# 130820_I_T_V_AriloRX_FINAL.net
KiCad netlist of a schematic drawn in EAGLE
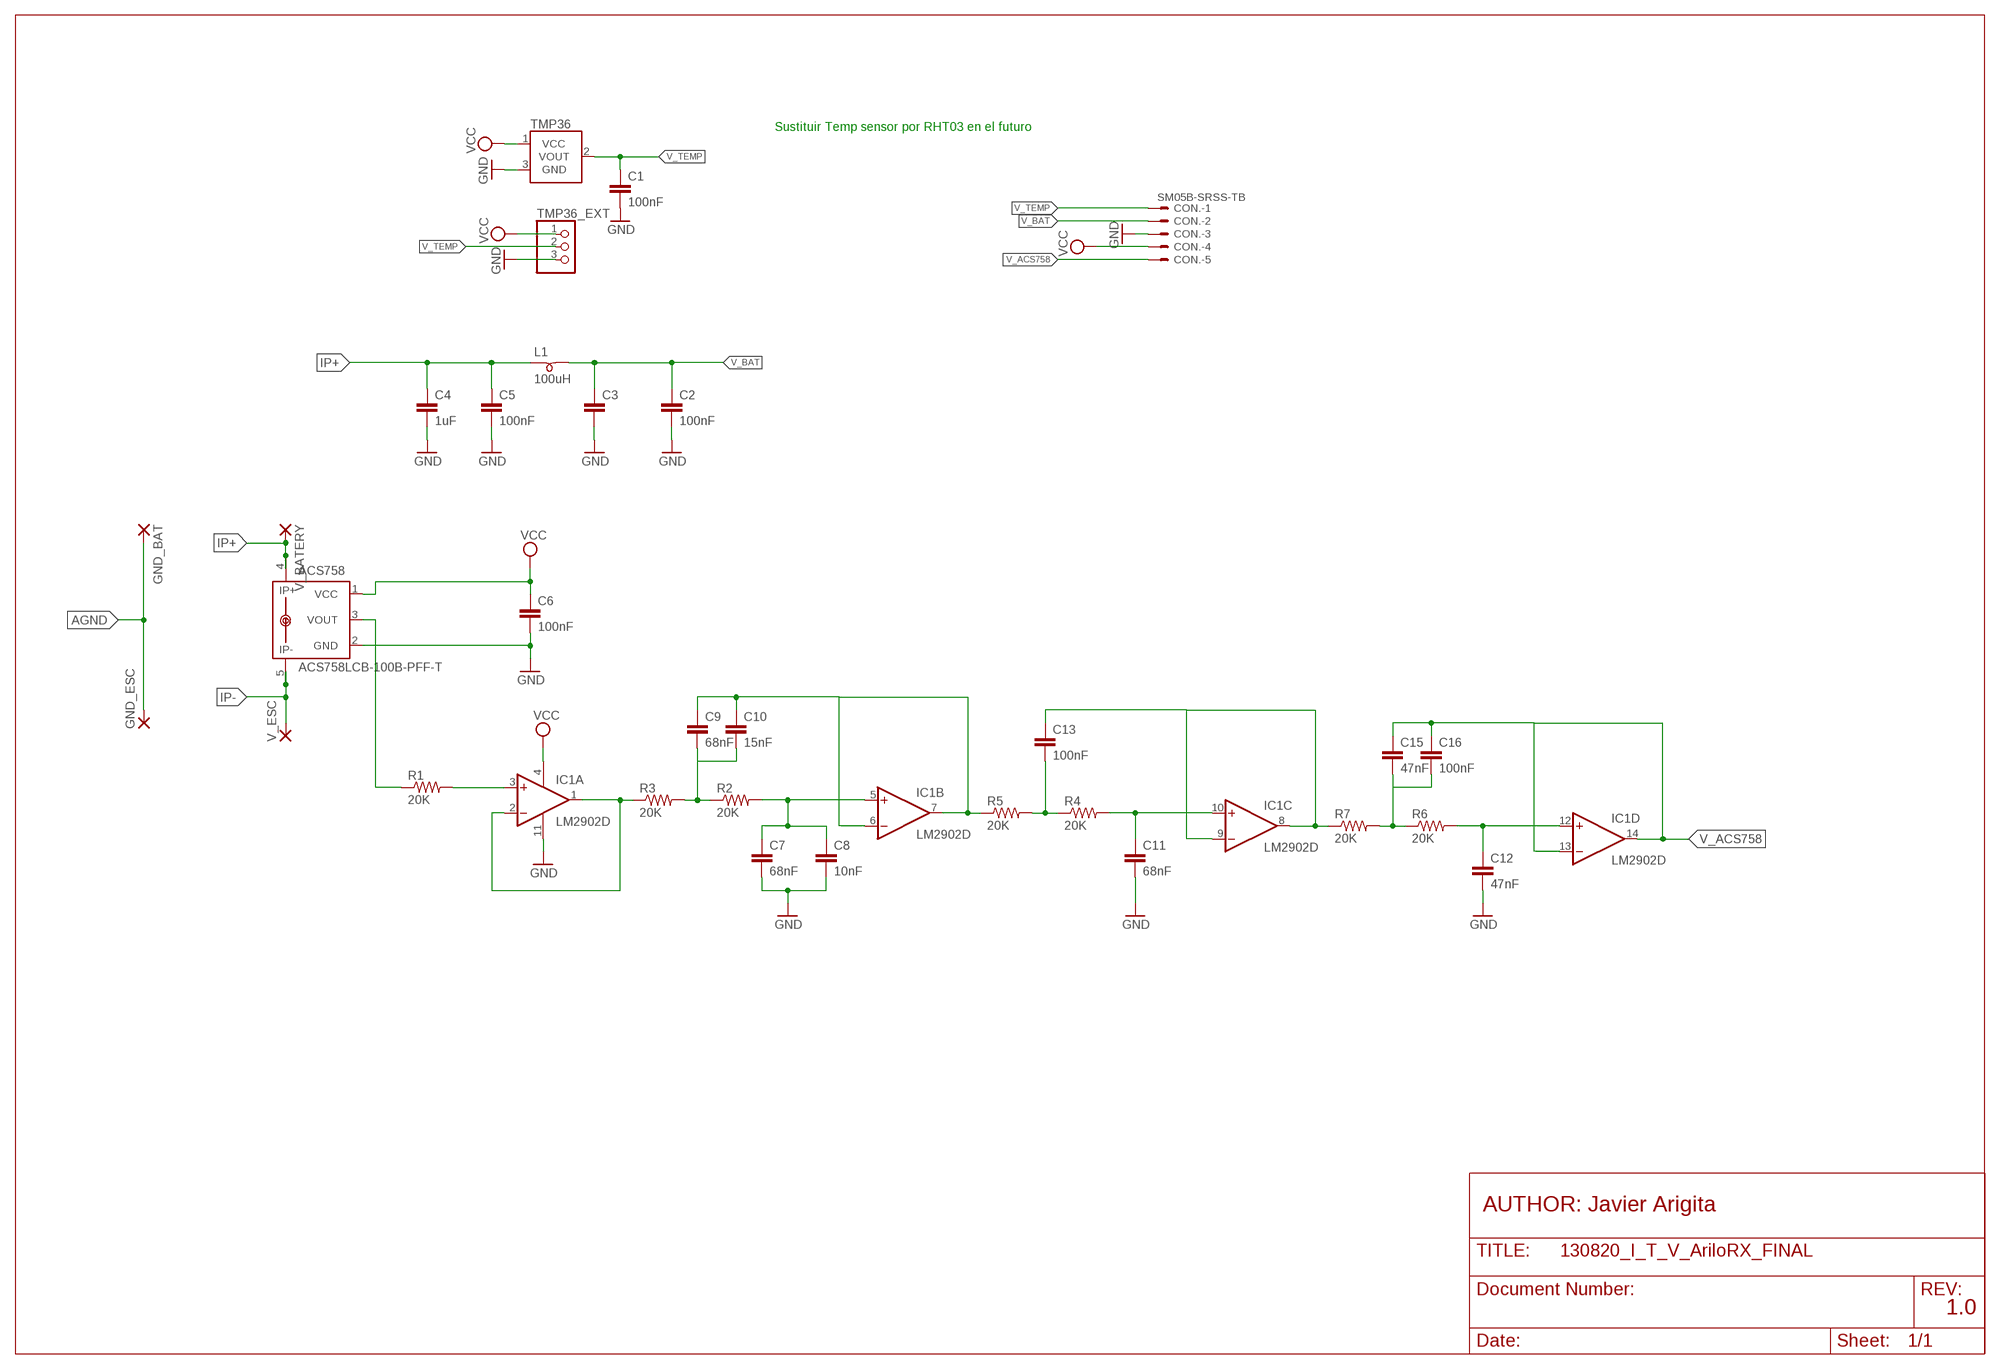
[diagram p0: schematic, sheet 1]

(export (version "E")
  (design (tool "Eeschema 10.0.6"))
  (components
    (comp (ref "ACS758")
      (value "ACS758LCB-100B-PFF-T")
      (footprint "eagle-import:CB-PFF")
      (libsource (lib "eagle-import") (part "ACS758LCB-100B-PFF-T"))
    )
    (comp (ref "C1")
      (value "100nF")
      (footprint "eagle-import:C0805")
      (libsource (lib "eagle-import") (part "C-EUC0805"))
    )
    (comp (ref "C2")
      (value "100nF")
      (footprint "eagle-import:C0805")
      (libsource (lib "eagle-import") (part "C-EUC0805"))
    )
    (comp (ref "C3")
      (value "C-EUC3216")
      (footprint "eagle-import:C3216")
      (libsource (lib "eagle-import") (part "C-EUC3216"))
    )
    (comp (ref "C4")
      (value "1uF")
      (footprint "eagle-import:C3216")
      (libsource (lib "eagle-import") (part "C-EUC3216"))
    )
    (comp (ref "C5")
      (value "100nF")
      (footprint "eagle-import:C0805")
      (libsource (lib "eagle-import") (part "C-EUC0805"))
    )
    (comp (ref "C6")
      (value "100nF")
      (footprint "eagle-import:C0805")
      (libsource (lib "eagle-import") (part "C-EUC0805"))
    )
    (comp (ref "C7")
      (value "68nF")
      (footprint "eagle-import:C0805")
      (libsource (lib "eagle-import") (part "C-EUC0805"))
    )
    (comp (ref "C8")
      (value "10nF")
      (footprint "eagle-import:C0805")
      (libsource (lib "eagle-import") (part "C-EUC0805"))
    )
    (comp (ref "C9")
      (value "68nF")
      (footprint "eagle-import:C0805")
      (libsource (lib "eagle-import") (part "C-EUC0805"))
    )
    (comp (ref "C10")
      (value "15nF")
      (footprint "eagle-import:C0805")
      (libsource (lib "eagle-import") (part "C-EUC0805"))
    )
    (comp (ref "C11")
      (value "68nF")
      (footprint "eagle-import:C0805")
      (libsource (lib "eagle-import") (part "C-EUC0805"))
    )
    (comp (ref "C12")
      (value "47nF")
      (footprint "eagle-import:C0805")
      (libsource (lib "eagle-import") (part "C-EUC0805"))
    )
    (comp (ref "C13")
      (value "100nF")
      (footprint "eagle-import:C0805")
      (libsource (lib "eagle-import") (part "C-EUC0805"))
    )
    (comp (ref "C15")
      (value "47nF")
      (footprint "eagle-import:C0805")
      (libsource (lib "eagle-import") (part "C-EUC0805"))
    )
    (comp (ref "C16")
      (value "100nF")
      (footprint "eagle-import:C0805")
      (libsource (lib "eagle-import") (part "C-EUC0805"))
    )
    (comp (ref "CON.")
      (value "SM05B-SRSS-TB")
      (footprint "eagle-import:SM05B-SRSS-TB")
      (libsource (lib "eagle-import") (part "?M05B-SRSS-TBS"))
    )
    (comp (ref "GND_BAT")
      (value "SMD5")
      (footprint "eagle-import:SMD2,54-5,08")
      (libsource (lib "eagle-import") (part "SMD5"))
    )
    (comp (ref "GND_ESC")
      (value "SMD5")
      (footprint "eagle-import:SMD2,54-5,08")
      (libsource (lib "eagle-import") (part "SMD5"))
    )
    (comp (ref "IC1")
      (value "LM2902D")
      (footprint "eagle-import:SO14")
      (libsource (lib "eagle-import") (part "LM2902D"))
    )
    (comp (ref "L1")
      (value "100uH")
      (footprint "eagle-import:SM-B5")
      (libsource (lib "eagle-import") (part "SM-B5"))
    )
    (comp (ref "R1")
      (value "20K")
      (footprint "eagle-import:R0805")
      (libsource (lib "eagle-import") (part "RESISTOR0805"))
    )
    (comp (ref "R2")
      (value "20K")
      (footprint "eagle-import:R0805")
      (libsource (lib "eagle-import") (part "RESISTOR0805"))
    )
    (comp (ref "R3")
      (value "20K")
      (footprint "eagle-import:R0805")
      (libsource (lib "eagle-import") (part "RESISTOR0805"))
    )
    (comp (ref "R4")
      (value "20K")
      (footprint "eagle-import:R0805")
      (libsource (lib "eagle-import") (part "RESISTOR0805"))
    )
    (comp (ref "R5")
      (value "20K")
      (footprint "eagle-import:R0805")
      (libsource (lib "eagle-import") (part "RESISTOR0805"))
    )
    (comp (ref "R6")
      (value "20K")
      (footprint "eagle-import:R0805")
      (libsource (lib "eagle-import") (part "RESISTOR0805"))
    )
    (comp (ref "R7")
      (value "20K")
      (footprint "eagle-import:R0805")
      (libsource (lib "eagle-import") (part "RESISTOR0805"))
    )
    (comp (ref "TMP36")
      (value "TMP36GT9")
      (footprint "eagle-import:TO-92")
      (libsource (lib "eagle-import") (part "TMP36GT9"))
    )
    (comp (ref "TMP36_EXT")
      (value "PINHD-1X3")
      (footprint "eagle-import:1X03")
      (libsource (lib "eagle-import") (part "PINHD-1X3"))
    )
    (comp (ref "V_BATERY")
      (value "SMD5")
      (footprint "eagle-import:SMD2,54-5,08")
      (libsource (lib "eagle-import") (part "SMD5"))
    )
    (comp (ref "V_ESC")
      (value "SMD5")
      (footprint "eagle-import:SMD2,54-5,08")
      (libsource (lib "eagle-import") (part "SMD5"))
    )
  )
  (nets
    (net (code "1") (name "AGND") (class "Default")
      (node (ref "GND_BAT") (pin "1") (pinfunction "P_1") (pintype "passive"))
      (node (ref "GND_ESC") (pin "1") (pinfunction "P_1") (pintype "passive"))
    )
    (net (code "2") (name "GND") (class "Default")
      (node (ref "ACS758") (pin "2") (pinfunction "GND_2") (pintype "power_in"))
      (node (ref "C1") (pin "2") (pinfunction "2_2") (pintype "passive"))
      (node (ref "C11") (pin "2") (pinfunction "2_2") (pintype "passive"))
      (node (ref "C12") (pin "2") (pinfunction "2_2") (pintype "passive"))
      (node (ref "C2") (pin "2") (pinfunction "2_2") (pintype "passive"))
      (node (ref "C3") (pin "2") (pinfunction "2_2") (pintype "passive"))
      (node (ref "C4") (pin "2") (pinfunction "2_2") (pintype "passive"))
      (node (ref "C5") (pin "2") (pinfunction "2_2") (pintype "passive"))
      (node (ref "C6") (pin "2") (pinfunction "2_2") (pintype "passive"))
      (node (ref "C7") (pin "2") (pinfunction "2_2") (pintype "passive"))
      (node (ref "C8") (pin "2") (pinfunction "2_2") (pintype "passive"))
      (node (ref "CON.") (pin "3") (pinfunction "S_3") (pintype "passive"))
      (node (ref "IC1") (pin "11") (pinfunction "V-_11") (pintype "power_in"))
      (node (ref "TMP36") (pin "3") (pinfunction "GND_3") (pintype "bidirectional"))
      (node (ref "TMP36_EXT") (pin "3") (pinfunction "3_3") (pintype "passive"))
    )
    (net (code "3") (name "IP+") (class "Default")
      (node (ref "ACS758") (pin "4") (pinfunction "IP+_4") (pintype "passive"))
      (node (ref "ACS758") (pin "IP+1") (pinfunction "IP+1_IP+1") (pintype "input"))
      (node (ref "C4") (pin "1") (pinfunction "1_1") (pintype "passive"))
      (node (ref "C5") (pin "1") (pinfunction "1_1") (pintype "passive"))
      (node (ref "L1") (pin "1") (pinfunction "1_1") (pintype "passive"))
      (node (ref "V_BATERY") (pin "1") (pinfunction "P_1") (pintype "passive"))
    )
    (net (code "4") (name "IP-") (class "Default")
      (node (ref "ACS758") (pin "5") (pinfunction "IP-_5") (pintype "passive"))
      (node (ref "ACS758") (pin "IP-1") (pinfunction "IP-1_IP-1") (pintype "input"))
      (node (ref "V_ESC") (pin "1") (pinfunction "P_1") (pintype "passive"))
    )
    (net (code "5") (name "Net-(ACS758-VOUT)") (class "Default")
      (node (ref "ACS758") (pin "3") (pinfunction "VOUT_3") (pintype "output"))
      (node (ref "R1") (pin "1") (pinfunction "1_1") (pintype "passive"))
    )
    (net (code "6") (name "Net-(C10-Pad2)") (class "Default")
      (node (ref "C10") (pin "2") (pinfunction "2_2") (pintype "passive"))
      (node (ref "C9") (pin "2") (pinfunction "2_2") (pintype "passive"))
      (node (ref "R2") (pin "1") (pinfunction "1_1") (pintype "passive"))
      (node (ref "R3") (pin "2") (pinfunction "2_2") (pintype "passive"))
    )
    (net (code "7") (name "Net-(C13-Pad2)") (class "Default")
      (node (ref "C13") (pin "2") (pinfunction "2_2") (pintype "passive"))
      (node (ref "R4") (pin "1") (pinfunction "1_1") (pintype "passive"))
      (node (ref "R5") (pin "2") (pinfunction "2_2") (pintype "passive"))
    )
    (net (code "8") (name "Net-(C15-Pad2)") (class "Default")
      (node (ref "C15") (pin "2") (pinfunction "2_2") (pintype "passive"))
      (node (ref "C16") (pin "2") (pinfunction "2_2") (pintype "passive"))
      (node (ref "R6") (pin "1") (pinfunction "1_1") (pintype "passive"))
      (node (ref "R7") (pin "2") (pinfunction "2_2") (pintype "passive"))
    )
    (net (code "9") (name "Net-(IC1A-+IN)") (class "Default")
      (node (ref "IC1") (pin "3") (pinfunction "+IN_3") (pintype "input"))
      (node (ref "R1") (pin "2") (pinfunction "2_2") (pintype "passive"))
    )
    (net (code "10") (name "Net-(IC1A--IN)") (class "Default")
      (node (ref "IC1") (pin "1") (pinfunction "OUT_1") (pintype "output"))
      (node (ref "IC1") (pin "2") (pinfunction "-IN_2") (pintype "input"))
      (node (ref "R3") (pin "1") (pinfunction "1_1") (pintype "passive"))
    )
    (net (code "11") (name "Net-(IC1B-+IN)") (class "Default")
      (node (ref "C7") (pin "1") (pinfunction "1_1") (pintype "passive"))
      (node (ref "C8") (pin "1") (pinfunction "1_1") (pintype "passive"))
      (node (ref "IC1") (pin "5") (pinfunction "+IN_5") (pintype "input"))
      (node (ref "R2") (pin "2") (pinfunction "2_2") (pintype "passive"))
    )
    (net (code "12") (name "Net-(IC1B--IN)") (class "Default")
      (node (ref "C10") (pin "1") (pinfunction "1_1") (pintype "passive"))
      (node (ref "C9") (pin "1") (pinfunction "1_1") (pintype "passive"))
      (node (ref "IC1") (pin "6") (pinfunction "-IN_6") (pintype "input"))
      (node (ref "IC1") (pin "7") (pinfunction "OUT_7") (pintype "output"))
      (node (ref "R5") (pin "1") (pinfunction "1_1") (pintype "passive"))
    )
    (net (code "13") (name "Net-(IC1C-+IN)") (class "Default")
      (node (ref "C11") (pin "1") (pinfunction "1_1") (pintype "passive"))
      (node (ref "IC1") (pin "10") (pinfunction "+IN_10") (pintype "input"))
      (node (ref "R4") (pin "2") (pinfunction "2_2") (pintype "passive"))
    )
    (net (code "14") (name "Net-(IC1C--IN)") (class "Default")
      (node (ref "C13") (pin "1") (pinfunction "1_1") (pintype "passive"))
      (node (ref "IC1") (pin "8") (pinfunction "OUT_8") (pintype "output"))
      (node (ref "IC1") (pin "9") (pinfunction "-IN_9") (pintype "input"))
      (node (ref "R7") (pin "1") (pinfunction "1_1") (pintype "passive"))
    )
    (net (code "15") (name "Net-(IC1D-+IN)") (class "Default")
      (node (ref "C12") (pin "1") (pinfunction "1_1") (pintype "passive"))
      (node (ref "IC1") (pin "12") (pinfunction "+IN_12") (pintype "input"))
      (node (ref "R6") (pin "2") (pinfunction "2_2") (pintype "passive"))
    )
    (net (code "16") (name "VCC") (class "Default")
      (node (ref "ACS758") (pin "1") (pinfunction "VCC_1") (pintype "power_in"))
      (node (ref "C6") (pin "1") (pinfunction "1_1") (pintype "passive"))
      (node (ref "CON.") (pin "4") (pinfunction "S_4") (pintype "passive"))
      (node (ref "IC1") (pin "4") (pinfunction "V+_4") (pintype "power_in"))
      (node (ref "TMP36") (pin "1") (pinfunction "VCC_1") (pintype "bidirectional"))
      (node (ref "TMP36_EXT") (pin "1") (pinfunction "1_1") (pintype "passive"))
    )
    (net (code "17") (name "V_ACS758") (class "Default")
      (node (ref "C15") (pin "1") (pinfunction "1_1") (pintype "passive"))
      (node (ref "C16") (pin "1") (pinfunction "1_1") (pintype "passive"))
      (node (ref "CON.") (pin "5") (pinfunction "S_5") (pintype "passive"))
      (node (ref "IC1") (pin "13") (pinfunction "-IN_13") (pintype "input"))
      (node (ref "IC1") (pin "14") (pinfunction "OUT_14") (pintype "output"))
    )
    (net (code "18") (name "V_BAT") (class "Default")
      (node (ref "C2") (pin "1") (pinfunction "1_1") (pintype "passive"))
      (node (ref "C3") (pin "1") (pinfunction "1_1") (pintype "passive"))
      (node (ref "CON.") (pin "2") (pinfunction "S_2") (pintype "passive"))
      (node (ref "L1") (pin "2") (pinfunction "2_2") (pintype "passive"))
    )
    (net (code "19") (name "V_TEMP") (class "Default")
      (node (ref "C1") (pin "1") (pinfunction "1_1") (pintype "passive"))
      (node (ref "CON.") (pin "1") (pinfunction "S_1") (pintype "passive"))
      (node (ref "TMP36") (pin "2") (pinfunction "VOUT_2") (pintype "bidirectional"))
      (node (ref "TMP36_EXT") (pin "2") (pinfunction "2_2") (pintype "passive"))
    )
  )
)
